# ModuleCarrier-ISM4343-WBM-L44-C-v1_0_0.net
KiCad netlist of a schematic drawn in EAGLE
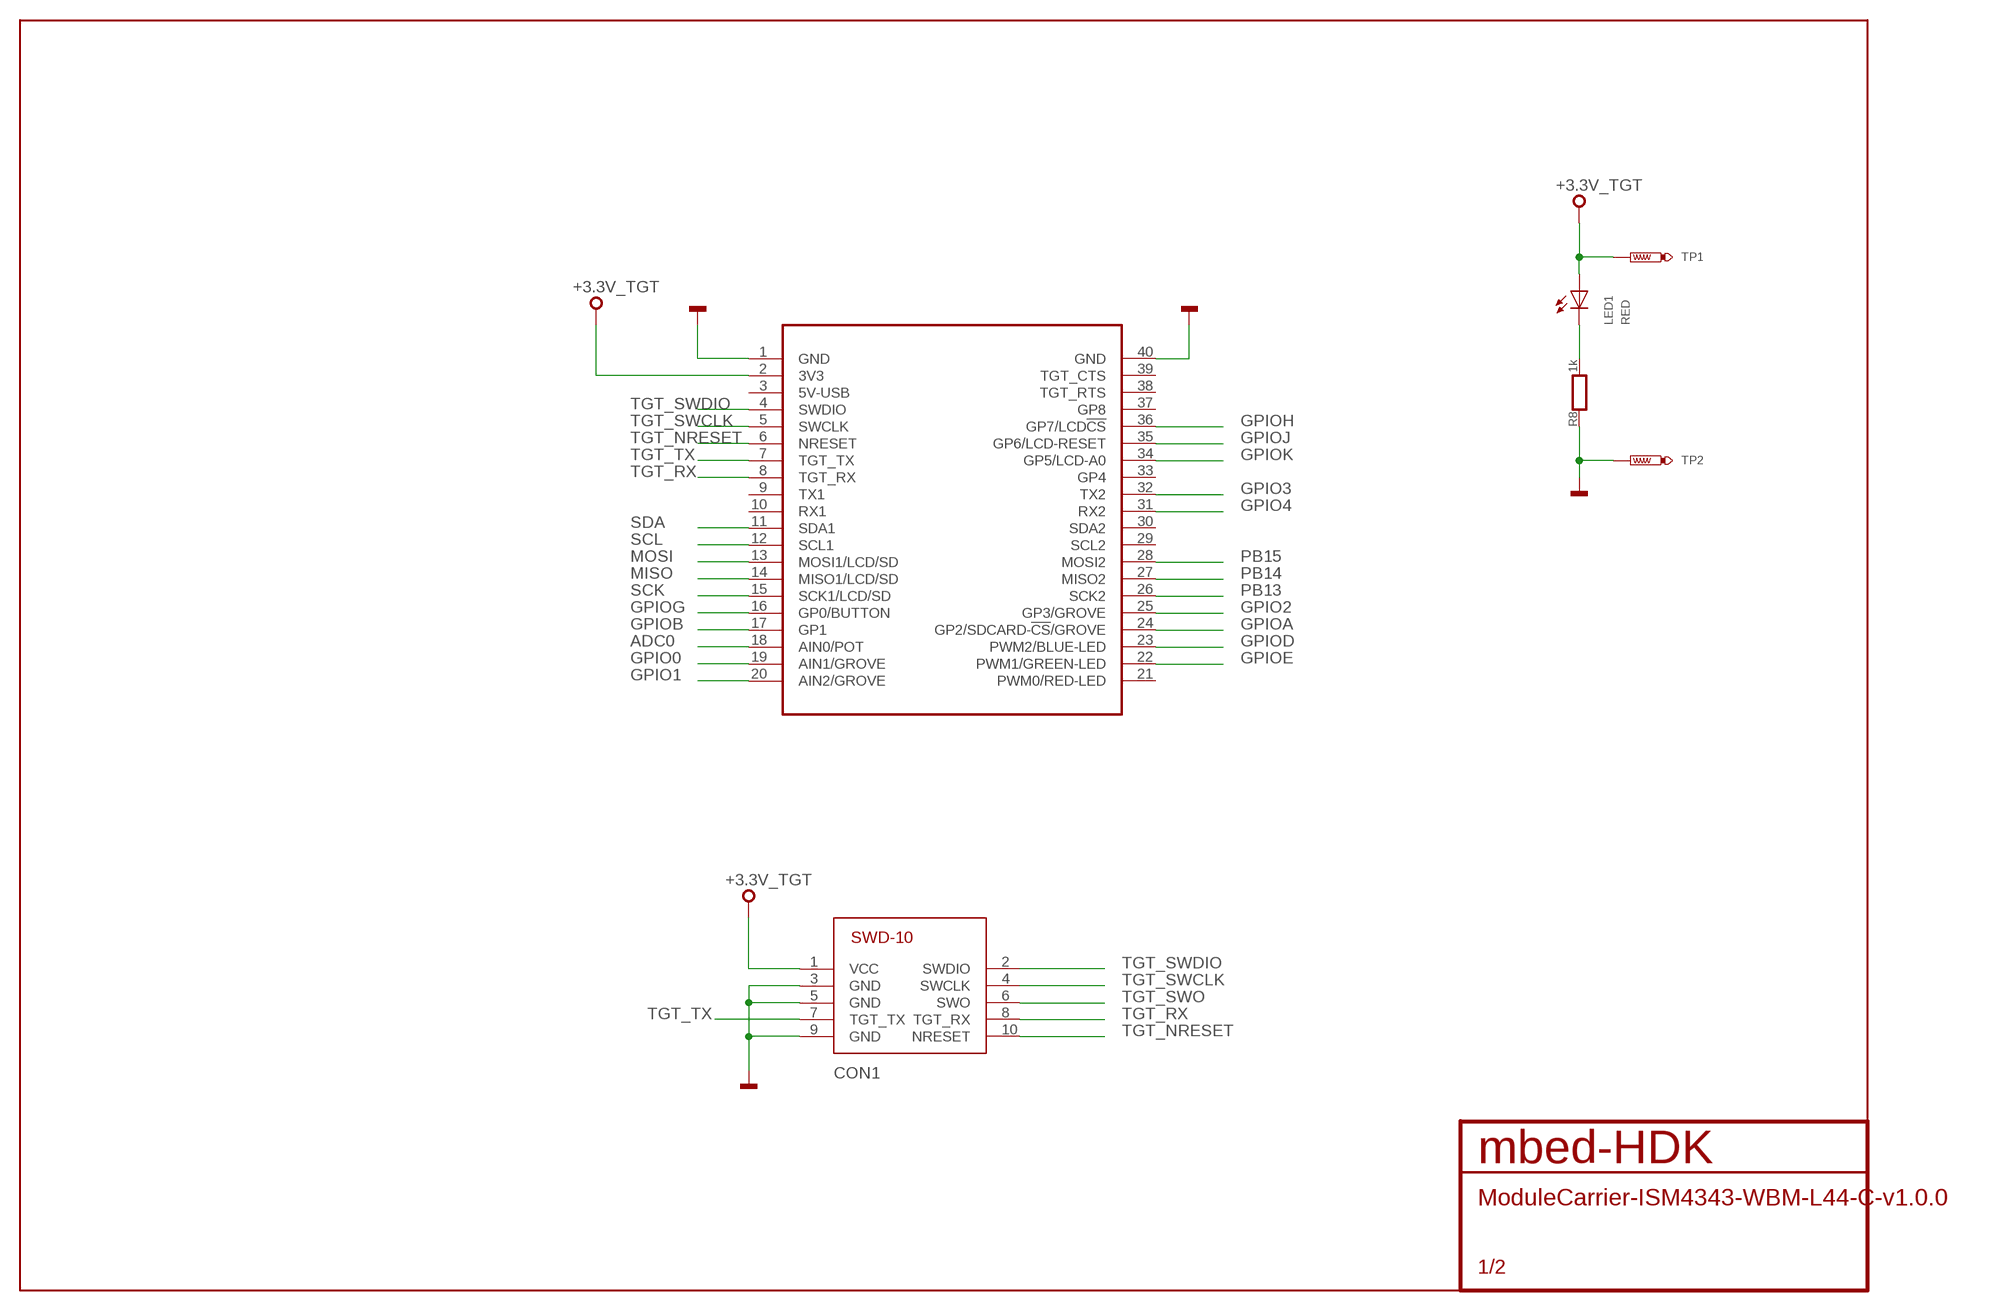
[diagram p0: schematic, sheet 1]
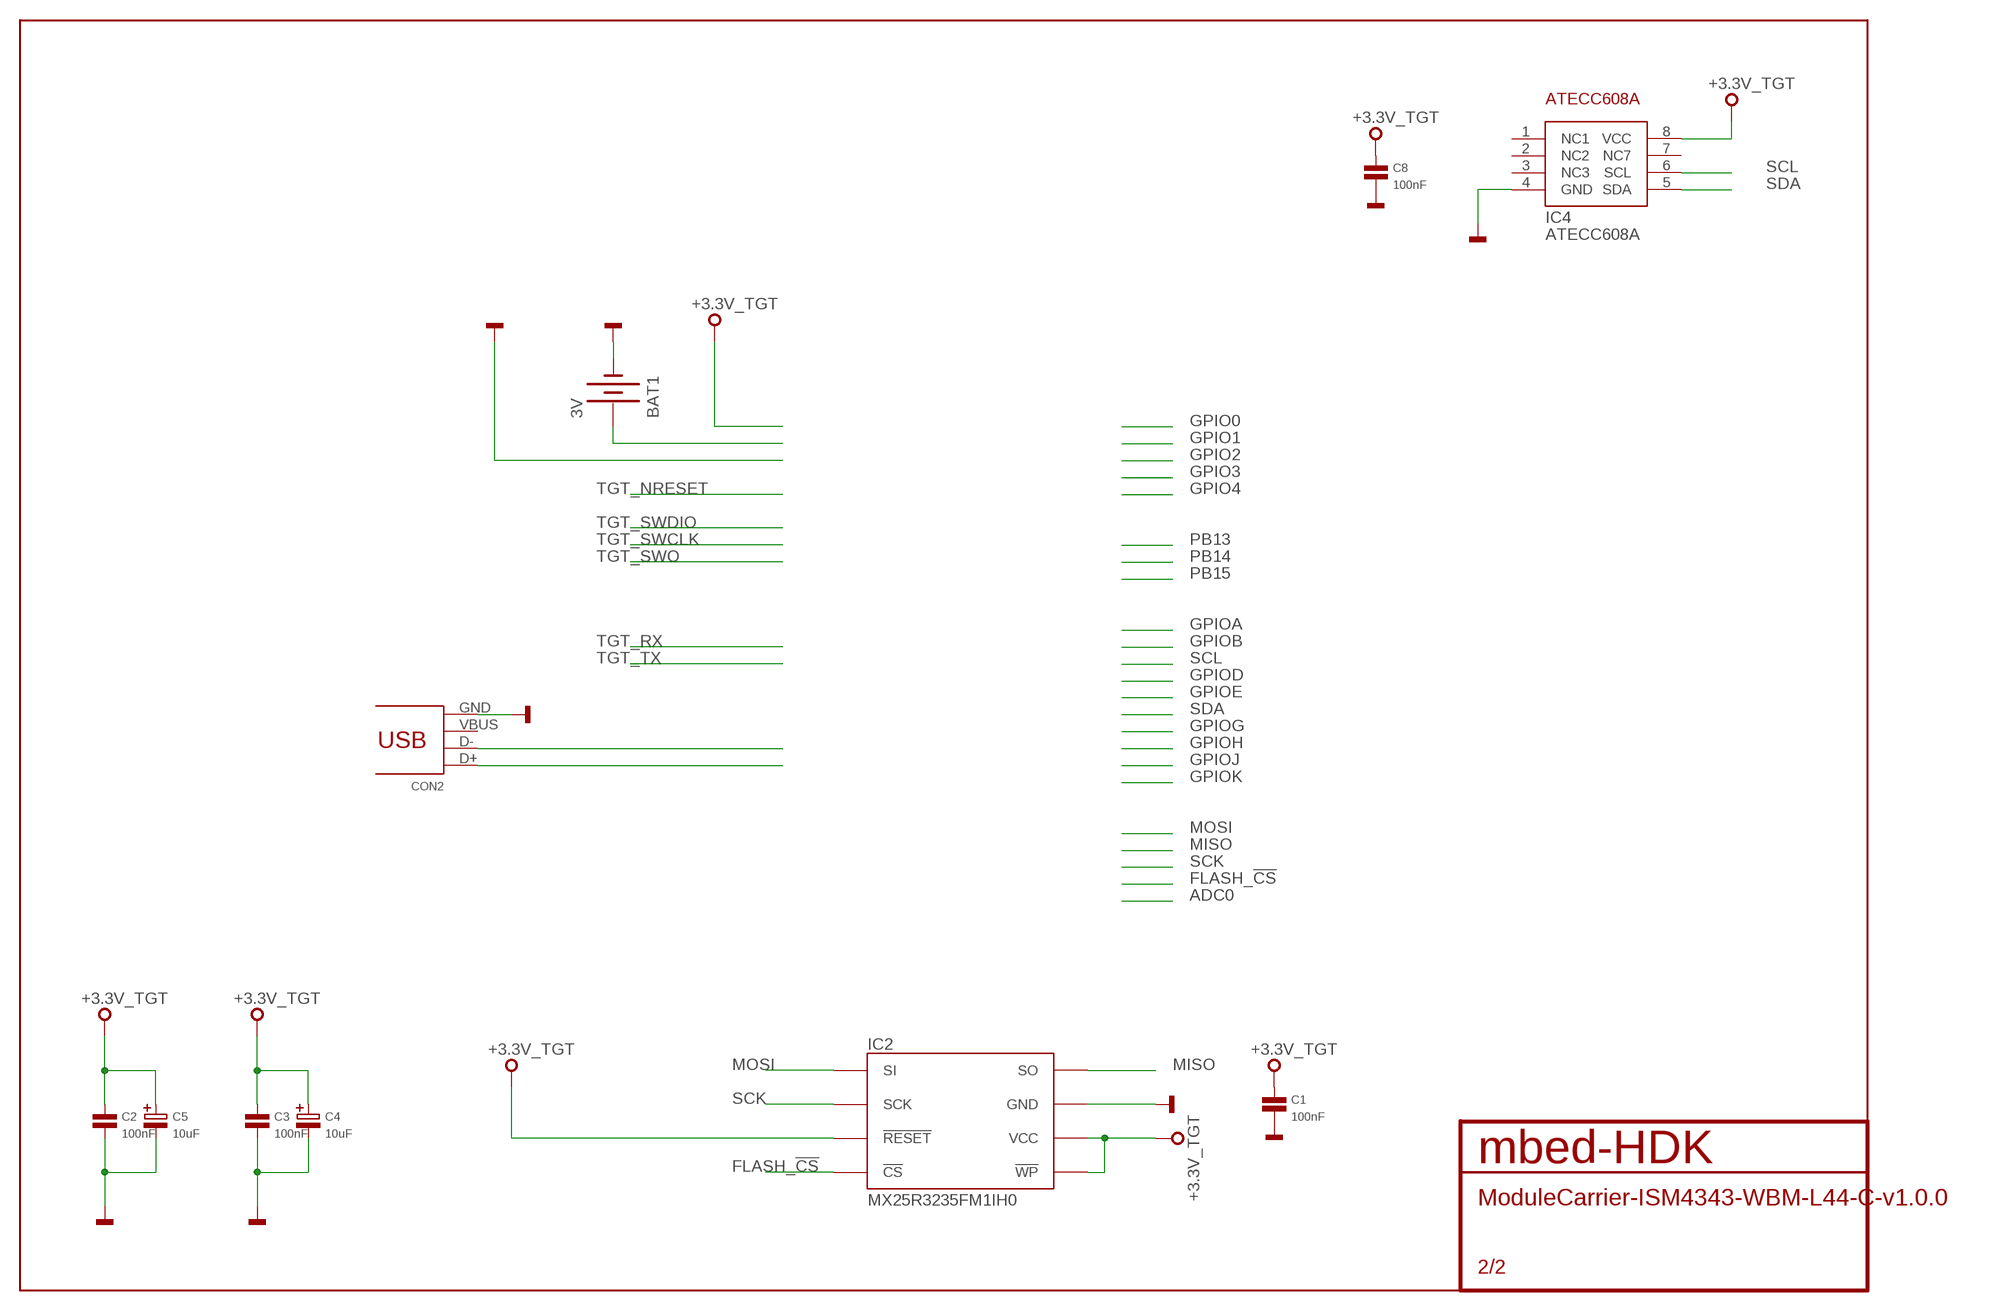
[diagram p1: schematic, sheet 2]

(export (version "E")
  (design (tool "Eeschema 10.0.6"))
  (components
    (comp (ref "CON1")
      (value "SWD-10/TC2050_SMD")
      (footprint "eagle-import:FTSH-105-02")
      (libsource (lib "eagle-import") (part "SWD-10/TC2050_SMD"))
    )
    (comp (ref "LED1")
      (value "RED")
      (footprint "eagle-import:CHIPLED_0603")
      (fields (field (name "MF") "Wurth Electronics Inc"))
      (libsource (lib "eagle-import") (part "SMD_LED0603"))
    )
    (comp (ref "MOD2")
      (value "MODULE_DAUGHTER")
      (footprint "eagle-import:MODULE_DAUGHTER")
      (libsource (lib "eagle-import") (part "MODULE_DAUGHTER"))
    )
    (comp (ref "R8")
      (value "1k")
      (footprint "eagle-import:0603")
      (libsource (lib "eagle-import") (part "RESISTOR0603"))
    )
    (comp (ref "TP1")
      (value "TEST-POINT-50R-PTH")
      (footprint "eagle-import:TP50-PTH")
      (libsource (lib "eagle-import") (part "TEST-POINT-50R-PTH"))
    )
    (comp (ref "TP2")
      (value "TEST-POINT-50R-PTH")
      (footprint "eagle-import:TP50-PTH")
      (libsource (lib "eagle-import") (part "TEST-POINT-50R-PTH"))
    )
    (comp (ref "BAT1")
      (value "3V")
      (footprint "eagle-import:BATTCON_12MM")
      (libsource (lib "eagle-import") (part "BATTERY12MM"))
    )
    (comp (ref "C1")
      (value "100nF")
      (footprint "eagle-import:0603")
      (libsource (lib "eagle-import") (part "CAPACITOR0603"))
    )
    (comp (ref "C2")
      (value "100nF")
      (footprint "eagle-import:0603")
      (libsource (lib "eagle-import") (part "CAPACITOR0603"))
    )
    (comp (ref "C3")
      (value "100nF")
      (footprint "eagle-import:0603")
      (libsource (lib "eagle-import") (part "CAPACITOR0603"))
    )
    (comp (ref "C4")
      (value "10uF")
      (footprint "eagle-import:SMC_B")
      (fields (field (name "MF") "Kemet"))
      (libsource (lib "eagle-import") (part "CAPACITOR-POLARISEDB"))
    )
    (comp (ref "C5")
      (value "10uF")
      (footprint "eagle-import:SMC_B")
      (fields (field (name "MF") "Kemet"))
      (libsource (lib "eagle-import") (part "CAPACITOR-POLARISEDB"))
    )
    (comp (ref "C8")
      (value "100nF")
      (footprint "eagle-import:0603")
      (libsource (lib "eagle-import") (part "CAPACITOR0603"))
    )
    (comp (ref "CON2")
      (value "10033526-N3212MLF")
      (footprint "eagle-import:USB-MINI-B-H")
      (fields (field (name "MF") "Amphenol FCI"))
      (libsource (lib "eagle-import") (part "10033526-N3212MLF"))
    )
    (comp (ref "IC2")
      (value "MX25R3235FM1IH0")
      (footprint "eagle-import:SO8")
      (fields (field (name "MF") "Macronix"))
      (libsource (lib "eagle-import") (part "MX25R3235FM1IH0"))
    )
    (comp (ref "IC4")
      (value "ATECC608A")
      (footprint "eagle-import:SO8")
      (libsource (lib "eagle-import") (part "ATECC608A"))
    )
  )
  (nets
    (net (code "1") (name "+3.3V_TGT") (class "Default")
      (node (ref "C1") (pin "1") (pinfunction "P$1_1") (pintype "passive"))
      (node (ref "C2") (pin "1") (pinfunction "P$1_1") (pintype "passive"))
      (node (ref "C3") (pin "1") (pinfunction "P$1_1") (pintype "passive"))
      (node (ref "C4") (pin "+") (pinfunction "+_+") (pintype "passive"))
      (node (ref "C5") (pin "+") (pinfunction "+_+") (pintype "passive"))
      (node (ref "C8") (pin "1") (pinfunction "P$1_1") (pintype "passive"))
      (node (ref "CON1") (pin "1") (pinfunction "VCC_1") (pintype "bidirectional"))
      (node (ref "IC2") (pin "3") (pinfunction "~{WP}_3") (pintype "bidirectional"))
      (node (ref "IC2") (pin "7") (pinfunction "~{RESET}_7") (pintype "bidirectional"))
      (node (ref "IC2") (pin "8") (pinfunction "VCC_8") (pintype "bidirectional"))
      (node (ref "IC4") (pin "8") (pinfunction "VCC_8") (pintype "bidirectional"))
      (node (ref "LED1") (pin "A") (pinfunction "A_A") (pintype "passive"))
      (node (ref "MOD2") (pin "2") (pinfunction "3V3_2") (pintype "bidirectional"))
      (node (ref "TP1") (pin "TP") (pinfunction "TP_TP") (pintype "input"))
    )
    (net (code "2") (name "ADC0") (class "Default")
      (node (ref "MOD2") (pin "18") (pinfunction "AIN0/POT_18") (pintype "bidirectional"))
    )
    (net (code "3") (name "FLASH_~{CS}") (class "Default")
      (node (ref "IC2") (pin "1") (pinfunction "~{CS}_1") (pintype "bidirectional"))
    )
    (net (code "4") (name "GND") (class "Default")
      (node (ref "BAT1") (pin "GND") (pinfunction "-_GND") (pintype "power_in"))
      (node (ref "C1") (pin "2") (pinfunction "P$2_2") (pintype "passive"))
      (node (ref "C2") (pin "2") (pinfunction "P$2_2") (pintype "passive"))
      (node (ref "C3") (pin "2") (pinfunction "P$2_2") (pintype "passive"))
      (node (ref "C4") (pin "-") (pinfunction "-_-") (pintype "passive"))
      (node (ref "C5") (pin "-") (pinfunction "-_-") (pintype "passive"))
      (node (ref "C8") (pin "2") (pinfunction "P$2_2") (pintype "passive"))
      (node (ref "CON1") (pin "3") (pinfunction "GND_3") (pintype "bidirectional"))
      (node (ref "CON1") (pin "5") (pinfunction "GND_5") (pintype "bidirectional"))
      (node (ref "CON1") (pin "9") (pinfunction "GND_9") (pintype "bidirectional"))
      (node (ref "CON2") (pin "GND") (pinfunction "GND_GND") (pintype "bidirectional"))
      (node (ref "IC2") (pin "4") (pinfunction "GND_4") (pintype "bidirectional"))
      (node (ref "IC4") (pin "4") (pinfunction "GND_4") (pintype "bidirectional"))
      (node (ref "MOD2") (pin "1") (pinfunction "GND_1") (pintype "bidirectional"))
      (node (ref "MOD2") (pin "40") (pinfunction "GND_40") (pintype "bidirectional"))
      (node (ref "R8") (pin "1") (pinfunction "P$1_1") (pintype "passive"))
      (node (ref "TP2") (pin "TP") (pinfunction "TP_TP") (pintype "input"))
    )
    (net (code "5") (name "GPIO0") (class "Default")
      (node (ref "MOD2") (pin "19") (pinfunction "AIN1/GROVE_19") (pintype "bidirectional"))
    )
    (net (code "6") (name "GPIO1") (class "Default")
      (node (ref "MOD2") (pin "20") (pinfunction "AIN2/GROVE_20") (pintype "bidirectional"))
    )
    (net (code "7") (name "GPIO2") (class "Default")
      (node (ref "MOD2") (pin "25") (pinfunction "GP3/GROVE_25") (pintype "bidirectional"))
    )
    (net (code "8") (name "GPIO3") (class "Default")
      (node (ref "MOD2") (pin "32") (pinfunction "TX2_32") (pintype "bidirectional"))
    )
    (net (code "9") (name "GPIO4") (class "Default")
      (node (ref "MOD2") (pin "31") (pinfunction "RX2_31") (pintype "bidirectional"))
    )
    (net (code "10") (name "GPIOA") (class "Default")
      (node (ref "MOD2") (pin "24") (pinfunction "GP2/SDCARD-~{CS}/GROVE_24") (pintype "bidirectional"))
    )
    (net (code "11") (name "GPIOB") (class "Default")
      (node (ref "MOD2") (pin "17") (pinfunction "GP1_17") (pintype "bidirectional"))
    )
    (net (code "12") (name "GPIOD") (class "Default")
      (node (ref "MOD2") (pin "23") (pinfunction "PWM2/BLUE-LED_23") (pintype "bidirectional"))
    )
    (net (code "13") (name "GPIOE") (class "Default")
      (node (ref "MOD2") (pin "22") (pinfunction "PWM1/GREEN-LED_22") (pintype "bidirectional"))
    )
    (net (code "14") (name "GPIOG") (class "Default")
      (node (ref "MOD2") (pin "16") (pinfunction "GP0/BUTTON_16") (pintype "bidirectional"))
    )
    (net (code "15") (name "GPIOH") (class "Default")
      (node (ref "MOD2") (pin "36") (pinfunction "GP7/LCD~{CS}_36") (pintype "bidirectional"))
    )
    (net (code "16") (name "GPIOJ") (class "Default")
      (node (ref "MOD2") (pin "35") (pinfunction "GP6/LCD-RESET_35") (pintype "bidirectional"))
    )
    (net (code "17") (name "GPIOK") (class "Default")
      (node (ref "MOD2") (pin "34") (pinfunction "GP5/LCD-A0_34") (pintype "bidirectional"))
    )
    (net (code "18") (name "MISO") (class "Default")
      (node (ref "IC2") (pin "2") (pinfunction "SO_2") (pintype "bidirectional"))
      (node (ref "MOD2") (pin "14") (pinfunction "MISO1/LCD/SD_14") (pintype "bidirectional"))
    )
    (net (code "19") (name "MOSI") (class "Default")
      (node (ref "IC2") (pin "5") (pinfunction "SI_5") (pintype "bidirectional"))
      (node (ref "MOD2") (pin "13") (pinfunction "MOSI1/LCD/SD_13") (pintype "bidirectional"))
    )
    (net (code "20") (name "Net-(R8-P$2)") (class "Default")
      (node (ref "LED1") (pin "C") (pinfunction "C_C") (pintype "passive"))
      (node (ref "R8") (pin "2") (pinfunction "P$2_2") (pintype "passive"))
    )
    (net (code "21") (name "PB13") (class "Default")
      (node (ref "MOD2") (pin "26") (pinfunction "SCK2_26") (pintype "bidirectional"))
    )
    (net (code "22") (name "PB14") (class "Default")
      (node (ref "MOD2") (pin "27") (pinfunction "MISO2_27") (pintype "bidirectional"))
    )
    (net (code "23") (name "PB15") (class "Default")
      (node (ref "MOD2") (pin "28") (pinfunction "MOSI2_28") (pintype "bidirectional"))
    )
    (net (code "24") (name "SCK") (class "Default")
      (node (ref "IC2") (pin "6") (pinfunction "SCK_6") (pintype "bidirectional"))
      (node (ref "MOD2") (pin "15") (pinfunction "SCK1/LCD/SD_15") (pintype "bidirectional"))
    )
    (net (code "25") (name "SCL") (class "Default")
      (node (ref "IC4") (pin "6") (pinfunction "SCL_6") (pintype "bidirectional"))
      (node (ref "MOD2") (pin "12") (pinfunction "SCL1_12") (pintype "bidirectional"))
    )
    (net (code "26") (name "SDA") (class "Default")
      (node (ref "IC4") (pin "5") (pinfunction "SDA_5") (pintype "bidirectional"))
      (node (ref "MOD2") (pin "11") (pinfunction "SDA1_11") (pintype "bidirectional"))
    )
    (net (code "27") (name "TGT_NRESET") (class "Default")
      (node (ref "CON1") (pin "10") (pinfunction "NRESET_10") (pintype "bidirectional"))
      (node (ref "MOD2") (pin "6") (pinfunction "NRESET_6") (pintype "bidirectional"))
    )
    (net (code "28") (name "TGT_RX") (class "Default")
      (node (ref "CON1") (pin "8") (pinfunction "TGT_RX_8") (pintype "bidirectional"))
      (node (ref "MOD2") (pin "8") (pinfunction "TGT_RX_8") (pintype "bidirectional"))
    )
    (net (code "29") (name "TGT_SWCLK") (class "Default")
      (node (ref "CON1") (pin "4") (pinfunction "SWCLK_4") (pintype "bidirectional"))
      (node (ref "MOD2") (pin "5") (pinfunction "SWCLK_5") (pintype "bidirectional"))
    )
    (net (code "30") (name "TGT_SWDIO") (class "Default")
      (node (ref "CON1") (pin "2") (pinfunction "SWDIO_2") (pintype "bidirectional"))
      (node (ref "MOD2") (pin "4") (pinfunction "SWDIO_4") (pintype "bidirectional"))
    )
    (net (code "31") (name "TGT_SWO") (class "Default")
      (node (ref "CON1") (pin "6") (pinfunction "SWO_6") (pintype "bidirectional"))
    )
    (net (code "32") (name "TGT_TX") (class "Default")
      (node (ref "CON1") (pin "7") (pinfunction "TGT_TX_7") (pintype "bidirectional"))
      (node (ref "MOD2") (pin "7") (pinfunction "TGT_TX_7") (pintype "bidirectional"))
    )
    (net (code "33") (name "unconnected-(BAT1-+-PadPWR@1)") (class "Default")
      (node (ref "BAT1") (pin "PWR@1") (pinfunction "+_PWR@1") (pintype "power_in"))
    )
    (net (code "34") (name "unconnected-(CON2-PadD+)") (class "Default")
      (node (ref "CON2") (pin "D+") (pinfunction "D+_D+") (pintype "bidirectional"))
    )
    (net (code "35") (name "unconnected-(CON2-PadD-)") (class "Default")
      (node (ref "CON2") (pin "D-") (pinfunction "D-_D-") (pintype "bidirectional"))
    )
    (net (code "36") (name "unconnected-(CON2-PadVBUS)") (class "Default")
      (node (ref "CON2") (pin "VBUS") (pinfunction "VBUS_VBUS") (pintype "bidirectional"))
    )
    (net (code "37") (name "unconnected-(IC4-NC1-Pad1)") (class "Default")
      (node (ref "IC4") (pin "1") (pinfunction "NC1_1") (pintype "bidirectional"))
    )
    (net (code "38") (name "unconnected-(IC4-NC2-Pad2)") (class "Default")
      (node (ref "IC4") (pin "2") (pinfunction "NC2_2") (pintype "bidirectional"))
    )
    (net (code "39") (name "unconnected-(IC4-NC3-Pad3)") (class "Default")
      (node (ref "IC4") (pin "3") (pinfunction "NC3_3") (pintype "bidirectional"))
    )
    (net (code "40") (name "unconnected-(IC4-NC7-Pad7)") (class "Default")
      (node (ref "IC4") (pin "7") (pinfunction "NC7_7") (pintype "bidirectional"))
    )
    (net (code "41") (name "unconnected-(MOD2-5V-USB-Pad3)") (class "Default")
      (node (ref "MOD2") (pin "3") (pinfunction "5V-USB_3") (pintype "bidirectional"))
    )
    (net (code "42") (name "unconnected-(MOD2-GP4-Pad33)") (class "Default")
      (node (ref "MOD2") (pin "33") (pinfunction "GP4_33") (pintype "bidirectional"))
    )
    (net (code "43") (name "unconnected-(MOD2-GP8-Pad37)") (class "Default")
      (node (ref "MOD2") (pin "37") (pinfunction "GP8_37") (pintype "bidirectional"))
    )
    (net (code "44") (name "unconnected-(MOD2-PWM0{slash}RED-LED-Pad21)") (class "Default")
      (node (ref "MOD2") (pin "21") (pinfunction "PWM0/RED-LED_21") (pintype "bidirectional"))
    )
    (net (code "45") (name "unconnected-(MOD2-RX1-Pad10)") (class "Default")
      (node (ref "MOD2") (pin "10") (pinfunction "RX1_10") (pintype "bidirectional"))
    )
    (net (code "46") (name "unconnected-(MOD2-SCL2-Pad29)") (class "Default")
      (node (ref "MOD2") (pin "29") (pinfunction "SCL2_29") (pintype "bidirectional"))
    )
    (net (code "47") (name "unconnected-(MOD2-SDA2-Pad30)") (class "Default")
      (node (ref "MOD2") (pin "30") (pinfunction "SDA2_30") (pintype "bidirectional"))
    )
    (net (code "48") (name "unconnected-(MOD2-TGT_CTS-Pad39)") (class "Default")
      (node (ref "MOD2") (pin "39") (pinfunction "TGT_CTS_39") (pintype "bidirectional"))
    )
    (net (code "49") (name "unconnected-(MOD2-TGT_RTS-Pad38)") (class "Default")
      (node (ref "MOD2") (pin "38") (pinfunction "TGT_RTS_38") (pintype "bidirectional"))
    )
    (net (code "50") (name "unconnected-(MOD2-TX1-Pad9)") (class "Default")
      (node (ref "MOD2") (pin "9") (pinfunction "TX1_9") (pintype "bidirectional"))
    )
  )
)
